# Constant_Power_Charging_Board_4_5.net
KiCad netlist of a schematic drawn in Altium Designer
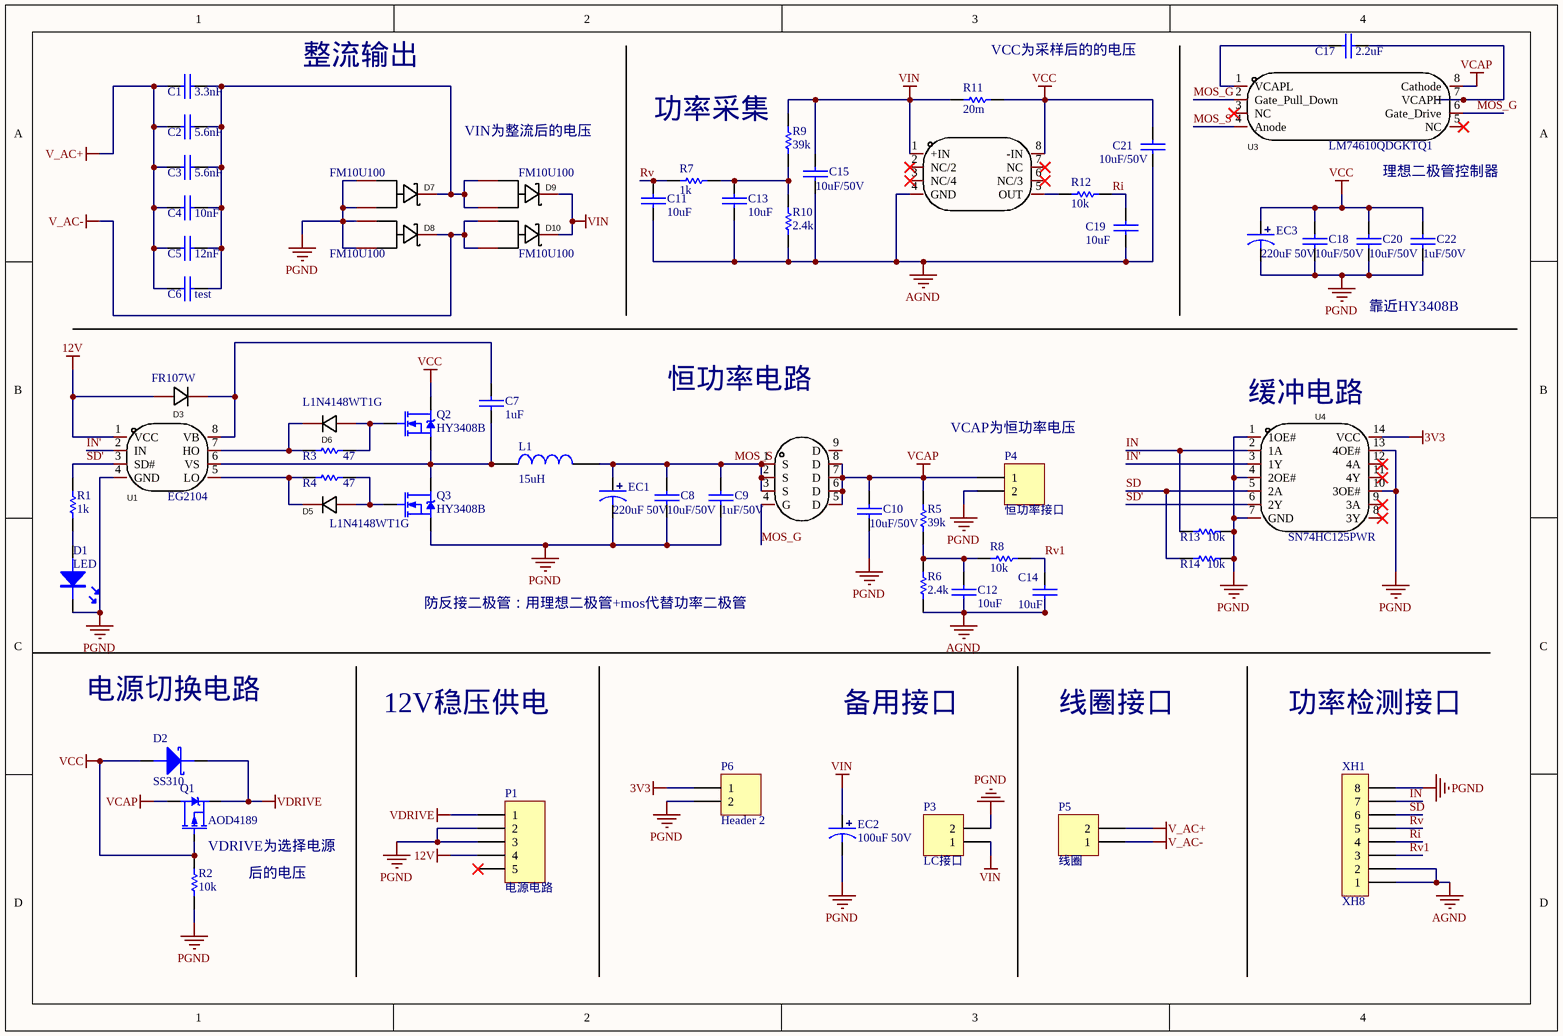
[diagram p0: Constant Power Charging Board 4.5.SchDoc]

(export (version "E")
  (design (tool "Eeschema 10.0.6"))
  (components
    (comp (ref "C1")
      (value "3.3nF")
      (footprint "谐振电容 P=10")
      (description "无极性电容")
      (libsource (lib "电容") (part "CAP"))
    )
    (comp (ref "C2")
      (value "5.6nF")
      (footprint "谐振电容 P=10")
      (description "无极性电容")
      (libsource (lib "电容") (part "CAP"))
    )
    (comp (ref "C3")
      (value "5.6nF")
      (footprint "谐振电容 P=10")
      (description "无极性电容")
      (libsource (lib "电容") (part "CAP"))
    )
    (comp (ref "C4")
      (value "10nF")
      (footprint "谐振电容 P=10")
      (description "无极性电容")
      (libsource (lib "电容") (part "CAP"))
    )
    (comp (ref "C5")
      (value "12nF")
      (footprint "谐振电容 P=10")
      (description "无极性电容")
      (libsource (lib "电容") (part "CAP"))
    )
    (comp (ref "C6")
      (value "test")
      (footprint "谐振电容 P=10")
      (description "无极性电容")
      (libsource (lib "电容") (part "CAP"))
    )
    (comp (ref "C7")
      (value "1uF")
      (footprint "0402C")
      (description "无极性电容")
      (libsource (lib "电容") (part "CAP"))
    )
    (comp (ref "C8")
      (value "10uF/50V")
      (footprint "0805C")
      (description "无极性电容")
      (libsource (lib "电容") (part "CAP"))
    )
    (comp (ref "C9")
      (value "1uF/50V")
      (footprint "0805C")
      (description "无极性电容")
      (libsource (lib "电容") (part "CAP"))
    )
    (comp (ref "C10")
      (value "10uF/50V")
      (footprint "0805C")
      (description "无极性电容")
      (libsource (lib "电容") (part "CAP"))
    )
    (comp (ref "C11")
      (value "10uF")
      (footprint "0603C")
      (description "无极性电容")
      (libsource (lib "电容") (part "CAP"))
    )
    (comp (ref "C12")
      (value "10uF")
      (footprint "0603C")
      (description "无极性电容")
      (libsource (lib "电容") (part "CAP"))
    )
    (comp (ref "C13")
      (value "10uF")
      (footprint "0603C")
      (description "无极性电容")
      (libsource (lib "电容") (part "CAP"))
    )
    (comp (ref "C14")
      (value "10uF")
      (footprint "0603C")
      (description "无极性电容")
      (libsource (lib "电容") (part "CAP"))
    )
    (comp (ref "C15")
      (value "10uF/50V")
      (footprint "0805C")
      (description "无极性电容")
      (libsource (lib "电容") (part "CAP"))
    )
    (comp (ref "C17")
      (value "2.2uF")
      (footprint "0402C")
      (description "无极性电容")
      (libsource (lib "电容") (part "CAP"))
    )
    (comp (ref "C18")
      (value "10uF/50V")
      (footprint "0805C")
      (description "无极性电容")
      (libsource (lib "电容") (part "CAP"))
    )
    (comp (ref "C19")
      (value "10uF")
      (footprint "0603C")
      (description "无极性电容")
      (libsource (lib "电容") (part "CAP"))
    )
    (comp (ref "C20")
      (value "10uF/50V")
      (footprint "0805C")
      (description "无极性电容")
      (libsource (lib "电容") (part "CAP"))
    )
    (comp (ref "C21")
      (value "10uF/50V")
      (footprint "0805C")
      (description "无极性电容")
      (libsource (lib "电容") (part "CAP"))
    )
    (comp (ref "C22")
      (value "1uF/50V")
      (footprint "0805C")
      (description "无极性电容")
      (libsource (lib "电容") (part "CAP"))
    )
    (comp (ref "D1") (value "LED") (footprint "LED-0603B") (libsource (lib "LED") (part "LED")))
    (comp (ref "D2")
      (value "SS310")
      (footprint "SMA/DO-214AC")
      (description "肖特基二极管")
      (libsource (lib "二极管") (part "DIODE SCHOTTKY"))
    )
    (comp (ref "D3")
      (value "FR107W")
      (footprint "FR107W")
      (fields (field (name "MANUFACTURER") "SHIKUES(时科)"))
      (libsource (lib "Schlib1") (part "FR107W"))
    )
    (comp (ref "D5")
      (value "L1N4148WT1G")
      (footprint "L1N4148WT1G")
      (fields (field (name "MANUFACTURER") "LRC(乐山无线电)"))
      (libsource (lib "Schlib1") (part "L1N4148WT1G"))
    )
    (comp (ref "D6")
      (value "L1N4148WT1G")
      (footprint "L1N4148WT1G")
      (fields (field (name "MANUFACTURER") "LRC(乐山无线电)"))
      (libsource (lib "Schlib1") (part "L1N4148WT1G"))
    )
    (comp (ref "D7")
      (value "FM10U100")
      (footprint "FM10U100")
      (fields (field (name "MANUFACTURER") "FMS(美丽微)"))
      (libsource (lib "Schlib1") (part "FM10U100"))
    )
    (comp (ref "D8")
      (value "FM10U100")
      (footprint "FM10U100")
      (fields (field (name "MANUFACTURER") "FMS(美丽微)"))
      (libsource (lib "Schlib1") (part "FM10U100"))
    )
    (comp (ref "D9")
      (value "FM10U100")
      (footprint "FM10U100")
      (fields (field (name "MANUFACTURER") "FMS(美丽微)"))
      (libsource (lib "Schlib1") (part "FM10U100"))
    )
    (comp (ref "D10")
      (value "FM10U100")
      (footprint "FM10U100")
      (fields (field (name "MANUFACTURER") "FMS(美丽微)"))
      (libsource (lib "Schlib1") (part "FM10U100"))
    )
    (comp (ref "EC1")
      (value "220uF 50V")
      (footprint "DIP-EC1.5X4X8")
      (description "直插电解电容")
      (libsource (lib "电容") (part "DIP_ECAP"))
    )
    (comp (ref "EC2")
      (value "100uF 50V")
      (footprint "DIP-EC6.3X11")
      (description "直插电解电容")
      (libsource (lib "电容") (part "DIP_ECAP"))
    )
    (comp (ref "EC3")
      (value "220uF 50V")
      (footprint "DIP-EC1.5X4X8")
      (description "直插电解电容")
      (libsource (lib "电容") (part "DIP_ECAP"))
    )
    (comp (ref "L1")
      (value "15uH")
      (footprint "0630L")
      (description "INDUCTOR")
      (libsource (lib "电感") (part "INDUCTOR"))
    )
    (comp (ref "P1")
      (value "电源电路")
      (footprint "12V稳压电路")
      (description "Header, 5-Pin")
      (fields (field (name "PUBLISHER") "Altium Limited"))
      (libsource (lib "Miscellaneous Connectors") (part "Header 5"))
    )
    (comp (ref "P3")
      (value "LC接口")
      (footprint "XT30U-M")
      (description "Header, 2-Pin")
      (fields (field (name "PUBLISHER") "Altium Limited"))
      (libsource (lib "Miscellaneous Connectors") (part "Header 2"))
    )
    (comp (ref "P4")
      (value "恒功率接口")
      (footprint "XT30U-M")
      (description "Header, 2-Pin")
      (fields (field (name "PUBLISHER") "Altium Limited"))
      (libsource (lib "") (part "Header 2_1"))
    )
    (comp (ref "P5")
      (value "线圈")
      (footprint "线圈接口")
      (description "Header, 2-Pin")
      (fields (field (name "PUBLISHER") "Altium Limited"))
      (libsource (lib "Miscellaneous Connectors") (part "Header 2"))
    )
    (comp (ref "P6")
      (value "Header 2")
      (footprint "HDR1X2")
      (description "Header, 2-Pin")
      (fields (field (name "PUBLISHER") "Altium Limited"))
      (libsource (lib "") (part "Header 2_1"))
    )
    (comp (ref "Q1")
      (value "AOD4189")
      (footprint "TO252")
      (description "P沟道场效应管")
      (libsource (lib "MOS管") (part "P-MOS"))
    )
    (comp (ref "Q2")
      (value "HY3408B")
      (footprint "TO-263-2L")
      (description "N沟道场效应管")
      (libsource (lib "MOS管") (part "N-MOS"))
    )
    (comp (ref "Q3")
      (value "HY3408B")
      (footprint "TO-263-2L")
      (description "N沟道场效应管")
      (libsource (lib "MOS管") (part "N-MOS"))
    )
    (comp (ref "Q4")
      (value "TPH1R403NL_C83440")
      (footprint "TPH1R403NL")
      (fields (field (name "MANUFACTURER") "TOSHIBA(东芝)") (field (name "MANUFACTURER PART") "TPH1R403NL"))
      (libsource (lib "Schlib1") (part "TPH1R403NL"))
    )
    (comp (ref "R1") (value "1k") (footprint "0402R") (libsource (lib "电阻") (part "RES")))
    (comp (ref "R2") (value "10k") (footprint "0402R") (libsource (lib "电阻") (part "RES")))
    (comp (ref "R3") (value "47") (footprint "0402R") (libsource (lib "电阻") (part "RES")))
    (comp (ref "R4") (value "47") (footprint "0402R") (libsource (lib "电阻") (part "RES")))
    (comp (ref "R5") (value "39k") (footprint "0402R") (libsource (lib "电阻") (part "RES")))
    (comp (ref "R6") (value "2.4k") (footprint "0402R") (libsource (lib "电阻") (part "RES")))
    (comp (ref "R7") (value "1k") (footprint "0402R") (libsource (lib "电阻") (part "RES")))
    (comp (ref "R8") (value "10k") (footprint "0402R") (libsource (lib "电阻") (part "RES")))
    (comp (ref "R9") (value "39k") (footprint "0402R") (libsource (lib "电阻") (part "RES")))
    (comp (ref "R10") (value "2.4k") (footprint "0402R") (libsource (lib "电阻") (part "RES")))
    (comp (ref "R11") (value "20m") (footprint "1206R") (libsource (lib "电阻") (part "RES")))
    (comp (ref "R12") (value "10k") (footprint "0402R") (libsource (lib "电阻") (part "RES")))
    (comp (ref "R13") (value "10k") (footprint "0402R") (libsource (lib "电阻") (part "RES")))
    (comp (ref "R14") (value "10k") (footprint "0402R") (libsource (lib "电阻") (part "RES")))
    (comp (ref "U1")
      (value "EG2104")
      (footprint "EG2104")
      (fields (field (name "MANUFACTURER") "EG(屹晶微)"))
      (libsource (lib "Schlib1") (part "EG2104"))
    )
    (comp (ref "U2")
      (value "AD8217BRMZ-RL")
      (footprint "AD8217BRMZ-RL")
      (fields (field (name "MANUFACTURER") "ADI(亚德诺)/LINEAR(凌特)"))
      (libsource (lib "Schlib1") (part "AD8217BRMZ-RL"))
    )
    (comp (ref "U3")
      (value "LM74610QDGKTQ1")
      (footprint "LM74610QDGKTQ1")
      (fields (field (name "MANUFACTURER") "TI(德州仪器)"))
      (libsource (lib "Schlib1") (part "LM74610QDGKTQ1"))
    )
    (comp (ref "U4")
      (value "SN74HC125PWR")
      (footprint "sn74hc125")
      (fields (field (name "MANUFACTURER") "TI(德州仪器)"))
      (libsource (lib "Schlib1") (part "SN74HC125PWR"))
    )
    (comp (ref "XH1") (value "XH8") (footprint "XH8/2.54mm/180") (libsource (lib "XH，VH") (part "XH8")))
  )
  (nets
    (net (code "1") (name "/IN") (class "Default")
      (node (ref "R13") (pin "1") (pinfunction "1_1") (pintype "passive"))
      (node (ref "U4") (pin "2") (pinfunction "1A_2") (pintype "passive"))
      (node (ref "XH1") (pin "7") (pinfunction "7_7") (pintype "passive"))
    )
    (net (code "2") (name "/IN'") (class "Default")
      (node (ref "U1") (pin "2") (pinfunction "IN_2") (pintype "passive"))
      (node (ref "U4") (pin "3") (pinfunction "1Y_3") (pintype "passive"))
    )
    (net (code "3") (name "/MOS_G") (class "Default")
      (node (ref "Q4") (pin "4") (pinfunction "G_4") (pintype "passive"))
      (node (ref "U3") (pin "2") (pinfunction "Gate_Pull_Down_2") (pintype "passive"))
      (node (ref "U3") (pin "6") (pinfunction "Gate_Drive_6") (pintype "passive"))
    )
    (net (code "4") (name "/MOS_S") (class "Default")
      (node (ref "C8") (pin "2") (pinfunction "2_2") (pintype "passive"))
      (node (ref "C9") (pin "2") (pinfunction "2_2") (pintype "passive"))
      (node (ref "EC1") (pin "1") (pinfunction "1_1") (pintype "passive"))
      (node (ref "L1") (pin "2") (pinfunction "2_2") (pintype "passive"))
      (node (ref "Q4") (pin "1") (pinfunction "S_1") (pintype "passive"))
      (node (ref "Q4") (pin "2") (pinfunction "S_2") (pintype "passive"))
      (node (ref "Q4") (pin "3") (pinfunction "S_3") (pintype "passive"))
      (node (ref "U3") (pin "4") (pinfunction "Anode_4") (pintype "passive"))
    )
    (net (code "5") (name "/Ri") (class "Default")
      (node (ref "C19") (pin "2") (pinfunction "2_2") (pintype "passive"))
      (node (ref "R12") (pin "1") (pinfunction "1_1") (pintype "passive"))
      (node (ref "XH1") (pin "4") (pinfunction "4_4") (pintype "passive"))
    )
    (net (code "6") (name "/Rv") (class "Default")
      (node (ref "C11") (pin "2") (pinfunction "2_2") (pintype "passive"))
      (node (ref "R7") (pin "1") (pinfunction "1_1") (pintype "passive"))
      (node (ref "XH1") (pin "5") (pinfunction "5_5") (pintype "passive"))
    )
    (net (code "7") (name "/Rv1") (class "Default")
      (node (ref "C14") (pin "2") (pinfunction "2_2") (pintype "passive"))
      (node (ref "R8") (pin "1") (pinfunction "1_1") (pintype "passive"))
      (node (ref "XH1") (pin "3") (pinfunction "3_3") (pintype "passive"))
    )
    (net (code "8") (name "/SD") (class "Default")
      (node (ref "R14") (pin "1") (pinfunction "1_1") (pintype "passive"))
      (node (ref "U4") (pin "5") (pinfunction "2A_5") (pintype "passive"))
      (node (ref "XH1") (pin "6") (pinfunction "6_6") (pintype "passive"))
    )
    (net (code "9") (name "/SD'") (class "Default")
      (node (ref "R1") (pin "2") (pinfunction "2_2") (pintype "passive"))
      (node (ref "U1") (pin "3") (pinfunction "SD#_3") (pintype "passive"))
      (node (ref "U4") (pin "6") (pinfunction "2Y_6") (pintype "passive"))
    )
    (net (code "10") (name "3V3") (class "Default")
      (node (ref "P6") (pin "1") (pinfunction "1_1") (pintype "passive"))
      (node (ref "U4") (pin "14") (pinfunction "VCC_14") (pintype "passive"))
    )
    (net (code "11") (name "12V") (class "Default")
      (node (ref "D3") (pin "2") (pinfunction "A_2") (pintype "passive"))
      (node (ref "P1") (pin "4") (pinfunction "4_4") (pintype "passive"))
      (node (ref "U1") (pin "1") (pinfunction "VCC_1") (pintype "passive"))
    )
    (net (code "12") (name "AGND") (class "Default")
      (node (ref "C11") (pin "1") (pinfunction "1_1") (pintype "passive"))
      (node (ref "C12") (pin "1") (pinfunction "1_1") (pintype "passive"))
      (node (ref "C13") (pin "1") (pinfunction "1_1") (pintype "passive"))
      (node (ref "C14") (pin "1") (pinfunction "1_1") (pintype "passive"))
      (node (ref "C15") (pin "1") (pinfunction "1_1") (pintype "passive"))
      (node (ref "C19") (pin "1") (pinfunction "1_1") (pintype "passive"))
      (node (ref "C21") (pin "1") (pinfunction "1_1") (pintype "passive"))
      (node (ref "R10") (pin "1") (pinfunction "1_1") (pintype "passive"))
      (node (ref "R6") (pin "1") (pinfunction "1_1") (pintype "passive"))
      (node (ref "U2") (pin "4") (pinfunction "GND_4") (pintype "passive"))
      (node (ref "XH1") (pin "1") (pinfunction "1_1") (pintype "passive"))
      (node (ref "XH1") (pin "2") (pinfunction "2_2") (pintype "passive"))
    )
    (net (code "13") (name "Net-(C12-Pad2)") (class "Default")
      (node (ref "C12") (pin "2") (pinfunction "2_2") (pintype "passive"))
      (node (ref "R5") (pin "1") (pinfunction "1_1") (pintype "passive"))
      (node (ref "R6") (pin "2") (pinfunction "2_2") (pintype "passive"))
      (node (ref "R8") (pin "2") (pinfunction "2_2") (pintype "passive"))
    )
    (net (code "14") (name "Net-(C13-Pad2)") (class "Default")
      (node (ref "C13") (pin "2") (pinfunction "2_2") (pintype "passive"))
      (node (ref "R10") (pin "2") (pinfunction "2_2") (pintype "passive"))
      (node (ref "R7") (pin "2") (pinfunction "2_2") (pintype "passive"))
      (node (ref "R9") (pin "1") (pinfunction "1_1") (pintype "passive"))
    )
    (net (code "15") (name "Net-(D1-PadA)") (class "Default")
      (node (ref "D1") (pin "A") (pinfunction "A_A") (pintype "passive"))
      (node (ref "R1") (pin "1") (pinfunction "1_1") (pintype "passive"))
    )
    (net (code "16") (name "Net-(D3-K)") (class "Default")
      (node (ref "C7") (pin "2") (pinfunction "2_2") (pintype "passive"))
      (node (ref "D3") (pin "1") (pinfunction "K_1") (pintype "passive"))
      (node (ref "U1") (pin "8") (pinfunction "VB_8") (pintype "passive"))
    )
    (net (code "17") (name "Net-(D5-A)") (class "Default")
      (node (ref "D5") (pin "2") (pinfunction "A_2") (pintype "passive"))
      (node (ref "Q3") (pin "G") (pinfunction "G_G") (pintype "passive"))
      (node (ref "R4") (pin "2") (pinfunction "2_2") (pintype "passive"))
    )
    (net (code "18") (name "Net-(D5-K)") (class "Default")
      (node (ref "D5") (pin "1") (pinfunction "K_1") (pintype "passive"))
      (node (ref "R4") (pin "1") (pinfunction "1_1") (pintype "passive"))
      (node (ref "U1") (pin "5") (pinfunction "LO_5") (pintype "passive"))
    )
    (net (code "19") (name "Net-(D6-A)") (class "Default")
      (node (ref "D6") (pin "2") (pinfunction "A_2") (pintype "passive"))
      (node (ref "Q2") (pin "G") (pinfunction "G_G") (pintype "passive"))
      (node (ref "R3") (pin "2") (pinfunction "2_2") (pintype "passive"))
    )
    (net (code "20") (name "Net-(D6-K)") (class "Default")
      (node (ref "D6") (pin "1") (pinfunction "K_1") (pintype "passive"))
      (node (ref "R3") (pin "1") (pinfunction "1_1") (pintype "passive"))
      (node (ref "U1") (pin "7") (pinfunction "HO_7") (pintype "passive"))
    )
    (net (code "21") (name "Net-(D7-C)") (class "Default")
      (node (ref "C1") (pin "2") (pinfunction "2_2") (pintype "passive"))
      (node (ref "C2") (pin "2") (pinfunction "2_2") (pintype "passive"))
      (node (ref "C3") (pin "2") (pinfunction "2_2") (pintype "passive"))
      (node (ref "C4") (pin "2") (pinfunction "2_2") (pintype "passive"))
      (node (ref "C5") (pin "2") (pinfunction "2_2") (pintype "passive"))
      (node (ref "C6") (pin "2") (pinfunction "2_2") (pintype "passive"))
      (node (ref "D7") (pin "2") (pinfunction "C_2") (pintype "passive"))
      (node (ref "D9") (pin "1") (pinfunction "A_1") (pintype "passive"))
      (node (ref "D9") (pin "3") (pinfunction "A_3") (pintype "passive"))
    )
    (net (code "22") (name "Net-(U1-VS)") (class "Default")
      (node (ref "C7") (pin "1") (pinfunction "1_1") (pintype "passive"))
      (node (ref "L1") (pin "1") (pinfunction "1_1") (pintype "passive"))
      (node (ref "Q2") (pin "S") (pinfunction "S_S") (pintype "passive"))
      (node (ref "Q3") (pin "D") (pinfunction "D_D") (pintype "passive"))
      (node (ref "U1") (pin "6") (pinfunction "VS_6") (pintype "passive"))
    )
    (net (code "23") (name "Net-(U2-OUT)") (class "Default")
      (node (ref "R12") (pin "2") (pinfunction "2_2") (pintype "passive"))
      (node (ref "U2") (pin "5") (pinfunction "OUT_5") (pintype "passive"))
    )
    (net (code "24") (name "Net-(U3-VCAPH)") (class "Default")
      (node (ref "C17") (pin "1") (pinfunction "1_1") (pintype "passive"))
      (node (ref "U3") (pin "7") (pinfunction "VCAPH_7") (pintype "passive"))
    )
    (net (code "25") (name "Net-(U3-VCAPL)") (class "Default")
      (node (ref "C17") (pin "2") (pinfunction "2_2") (pintype "passive"))
      (node (ref "U3") (pin "1") (pinfunction "VCAPL_1") (pintype "passive"))
    )
    (net (code "26") (name "PGND") (class "Default")
      (node (ref "C10") (pin "1") (pinfunction "1_1") (pintype "passive"))
      (node (ref "C18") (pin "1") (pinfunction "1_1") (pintype "passive"))
      (node (ref "C20") (pin "1") (pinfunction "1_1") (pintype "passive"))
      (node (ref "C22") (pin "1") (pinfunction "1_1") (pintype "passive"))
      (node (ref "C8") (pin "1") (pinfunction "1_1") (pintype "passive"))
      (node (ref "C9") (pin "1") (pinfunction "1_1") (pintype "passive"))
      (node (ref "D1") (pin "K") (pinfunction "K_K") (pintype "passive"))
      (node (ref "D7") (pin "1") (pinfunction "A_1") (pintype "passive"))
      (node (ref "D7") (pin "3") (pinfunction "A_3") (pintype "passive"))
      (node (ref "D8") (pin "1") (pinfunction "A_1") (pintype "passive"))
      (node (ref "D8") (pin "3") (pinfunction "A_3") (pintype "passive"))
      (node (ref "EC1") (pin "2") (pinfunction "2_2") (pintype "passive"))
      (node (ref "EC2") (pin "2") (pinfunction "2_2") (pintype "passive"))
      (node (ref "EC3") (pin "2") (pinfunction "2_2") (pintype "passive"))
      (node (ref "P1") (pin "2") (pinfunction "2_2") (pintype "passive"))
      (node (ref "P1") (pin "3") (pinfunction "3_3") (pintype "passive"))
      (node (ref "P3") (pin "2") (pinfunction "2_2") (pintype "passive"))
      (node (ref "P4") (pin "2") (pinfunction "2_2") (pintype "passive"))
      (node (ref "P6") (pin "2") (pinfunction "2_2") (pintype "passive"))
      (node (ref "Q3") (pin "S") (pinfunction "S_S") (pintype "passive"))
      (node (ref "R13") (pin "2") (pinfunction "2_2") (pintype "passive"))
      (node (ref "R14") (pin "2") (pinfunction "2_2") (pintype "passive"))
      (node (ref "R2") (pin "1") (pinfunction "1_1") (pintype "passive"))
      (node (ref "U1") (pin "4") (pinfunction "GND_4") (pintype "passive"))
      (node (ref "U4") (pin "1") (pinfunction "1OE#_1") (pintype "passive"))
      (node (ref "U4") (pin "10") (pinfunction "3OE#_10") (pintype "passive"))
      (node (ref "U4") (pin "13") (pinfunction "4OE#_13") (pintype "passive"))
      (node (ref "U4") (pin "4") (pinfunction "2OE#_4") (pintype "passive"))
      (node (ref "U4") (pin "7") (pinfunction "GND_7") (pintype "passive"))
      (node (ref "XH1") (pin "8") (pinfunction "8_8") (pintype "passive"))
    )
    (net (code "27") (name "VCAP") (class "Default")
      (node (ref "C10") (pin "2") (pinfunction "2_2") (pintype "passive"))
      (node (ref "P4") (pin "1") (pinfunction "1_1") (pintype "passive"))
      (node (ref "Q1") (pin "D") (pinfunction "D_D") (pintype "passive"))
      (node (ref "Q4") (pin "5") (pinfunction "D_5") (pintype "passive"))
      (node (ref "Q4") (pin "6") (pinfunction "D_6") (pintype "passive"))
      (node (ref "Q4") (pin "7") (pinfunction "D_7") (pintype "passive"))
      (node (ref "Q4") (pin "8") (pinfunction "D_8") (pintype "passive"))
      (node (ref "R5") (pin "2") (pinfunction "2_2") (pintype "passive"))
      (node (ref "U3") (pin "8") (pinfunction "Cathode_8") (pintype "passive"))
    )
    (net (code "28") (name "VCC") (class "Default")
      (node (ref "C18") (pin "2") (pinfunction "2_2") (pintype "passive"))
      (node (ref "C20") (pin "2") (pinfunction "2_2") (pintype "passive"))
      (node (ref "C21") (pin "2") (pinfunction "2_2") (pintype "passive"))
      (node (ref "C22") (pin "2") (pinfunction "2_2") (pintype "passive"))
      (node (ref "D2") (pin "A") (pinfunction "A_A") (pintype "passive"))
      (node (ref "EC3") (pin "1") (pinfunction "1_1") (pintype "passive"))
      (node (ref "Q1") (pin "G") (pinfunction "G_G") (pintype "passive"))
      (node (ref "Q2") (pin "D") (pinfunction "D_D") (pintype "passive"))
      (node (ref "R11") (pin "1") (pinfunction "1_1") (pintype "passive"))
      (node (ref "R2") (pin "2") (pinfunction "2_2") (pintype "passive"))
      (node (ref "U2") (pin "8") (pinfunction "-IN_8") (pintype "passive"))
    )
    (net (code "29") (name "VDRIVE") (class "Default")
      (node (ref "D2") (pin "K") (pinfunction "K_K") (pintype "passive"))
      (node (ref "P1") (pin "1") (pinfunction "1_1") (pintype "passive"))
      (node (ref "Q1") (pin "S") (pinfunction "S_S") (pintype "passive"))
    )
    (net (code "30") (name "VIN") (class "Default")
      (node (ref "C15") (pin "2") (pinfunction "2_2") (pintype "passive"))
      (node (ref "D10") (pin "2") (pinfunction "C_2") (pintype "passive"))
      (node (ref "D9") (pin "2") (pinfunction "C_2") (pintype "passive"))
      (node (ref "EC2") (pin "1") (pinfunction "1_1") (pintype "passive"))
      (node (ref "P3") (pin "1") (pinfunction "1_1") (pintype "passive"))
      (node (ref "R11") (pin "2") (pinfunction "2_2") (pintype "passive"))
      (node (ref "R9") (pin "2") (pinfunction "2_2") (pintype "passive"))
      (node (ref "U2") (pin "1") (pinfunction "+IN_1") (pintype "passive"))
    )
    (net (code "31") (name "V_AC+") (class "Default")
      (node (ref "C1") (pin "1") (pinfunction "1_1") (pintype "passive"))
      (node (ref "C2") (pin "1") (pinfunction "1_1") (pintype "passive"))
      (node (ref "C3") (pin "1") (pinfunction "1_1") (pintype "passive"))
      (node (ref "C4") (pin "1") (pinfunction "1_1") (pintype "passive"))
      (node (ref "C5") (pin "1") (pinfunction "1_1") (pintype "passive"))
      (node (ref "C6") (pin "1") (pinfunction "1_1") (pintype "passive"))
      (node (ref "P5") (pin "2") (pinfunction "2_2") (pintype "passive"))
    )
    (net (code "32") (name "V_AC-") (class "Default")
      (node (ref "D10") (pin "1") (pinfunction "A_1") (pintype "passive"))
      (node (ref "D10") (pin "3") (pinfunction "A_3") (pintype "passive"))
      (node (ref "D8") (pin "2") (pinfunction "C_2") (pintype "passive"))
      (node (ref "P5") (pin "1") (pinfunction "1_1") (pintype "passive"))
    )
    (net (code "33") (name "unconnected-(P1-Pad5)") (class "Default")
      (node (ref "P1") (pin "5") (pinfunction "5_5") (pintype "passive+no_connect"))
    )
    (net (code "34") (name "unconnected-(Q4-D-Pad9)") (class "Default")
      (node (ref "Q4") (pin "9") (pinfunction "D_9") (pintype "passive"))
    )
    (net (code "35") (name "unconnected-(U2-NC-Pad7)") (class "Default")
      (node (ref "U2") (pin "7") (pinfunction "NC_7") (pintype "passive+no_connect"))
    )
    (net (code "36") (name "unconnected-(U2-NC{slash}2-Pad2)") (class "Default")
      (node (ref "U2") (pin "2") (pinfunction "NC/2_2") (pintype "passive+no_connect"))
    )
    (net (code "37") (name "unconnected-(U2-NC{slash}3-Pad6)") (class "Default")
      (node (ref "U2") (pin "6") (pinfunction "NC/3_6") (pintype "passive+no_connect"))
    )
    (net (code "38") (name "unconnected-(U2-NC{slash}4-Pad3)") (class "Default")
      (node (ref "U2") (pin "3") (pinfunction "NC/4_3") (pintype "passive+no_connect"))
    )
    (net (code "39") (name "unconnected-(U3-NC-Pad3)") (class "Default")
      (node (ref "U3") (pin "3") (pinfunction "NC_3") (pintype "passive+no_connect"))
    )
    (net (code "40") (name "unconnected-(U3-NC-Pad5)") (class "Default")
      (node (ref "U3") (pin "5") (pinfunction "NC_5") (pintype "passive+no_connect"))
    )
    (net (code "41") (name "unconnected-(U4-3A-Pad9)") (class "Default")
      (node (ref "U4") (pin "9") (pinfunction "3A_9") (pintype "passive+no_connect"))
    )
    (net (code "42") (name "unconnected-(U4-3Y-Pad8)") (class "Default")
      (node (ref "U4") (pin "8") (pinfunction "3Y_8") (pintype "passive+no_connect"))
    )
    (net (code "43") (name "unconnected-(U4-4A-Pad12)") (class "Default")
      (node (ref "U4") (pin "12") (pinfunction "4A_12") (pintype "passive+no_connect"))
    )
    (net (code "44") (name "unconnected-(U4-4Y-Pad11)") (class "Default")
      (node (ref "U4") (pin "11") (pinfunction "4Y_11") (pintype "passive+no_connect"))
    )
  )
)
